# TestBench_rev3_6.net
KiCad netlist of a schematic drawn in EAGLE
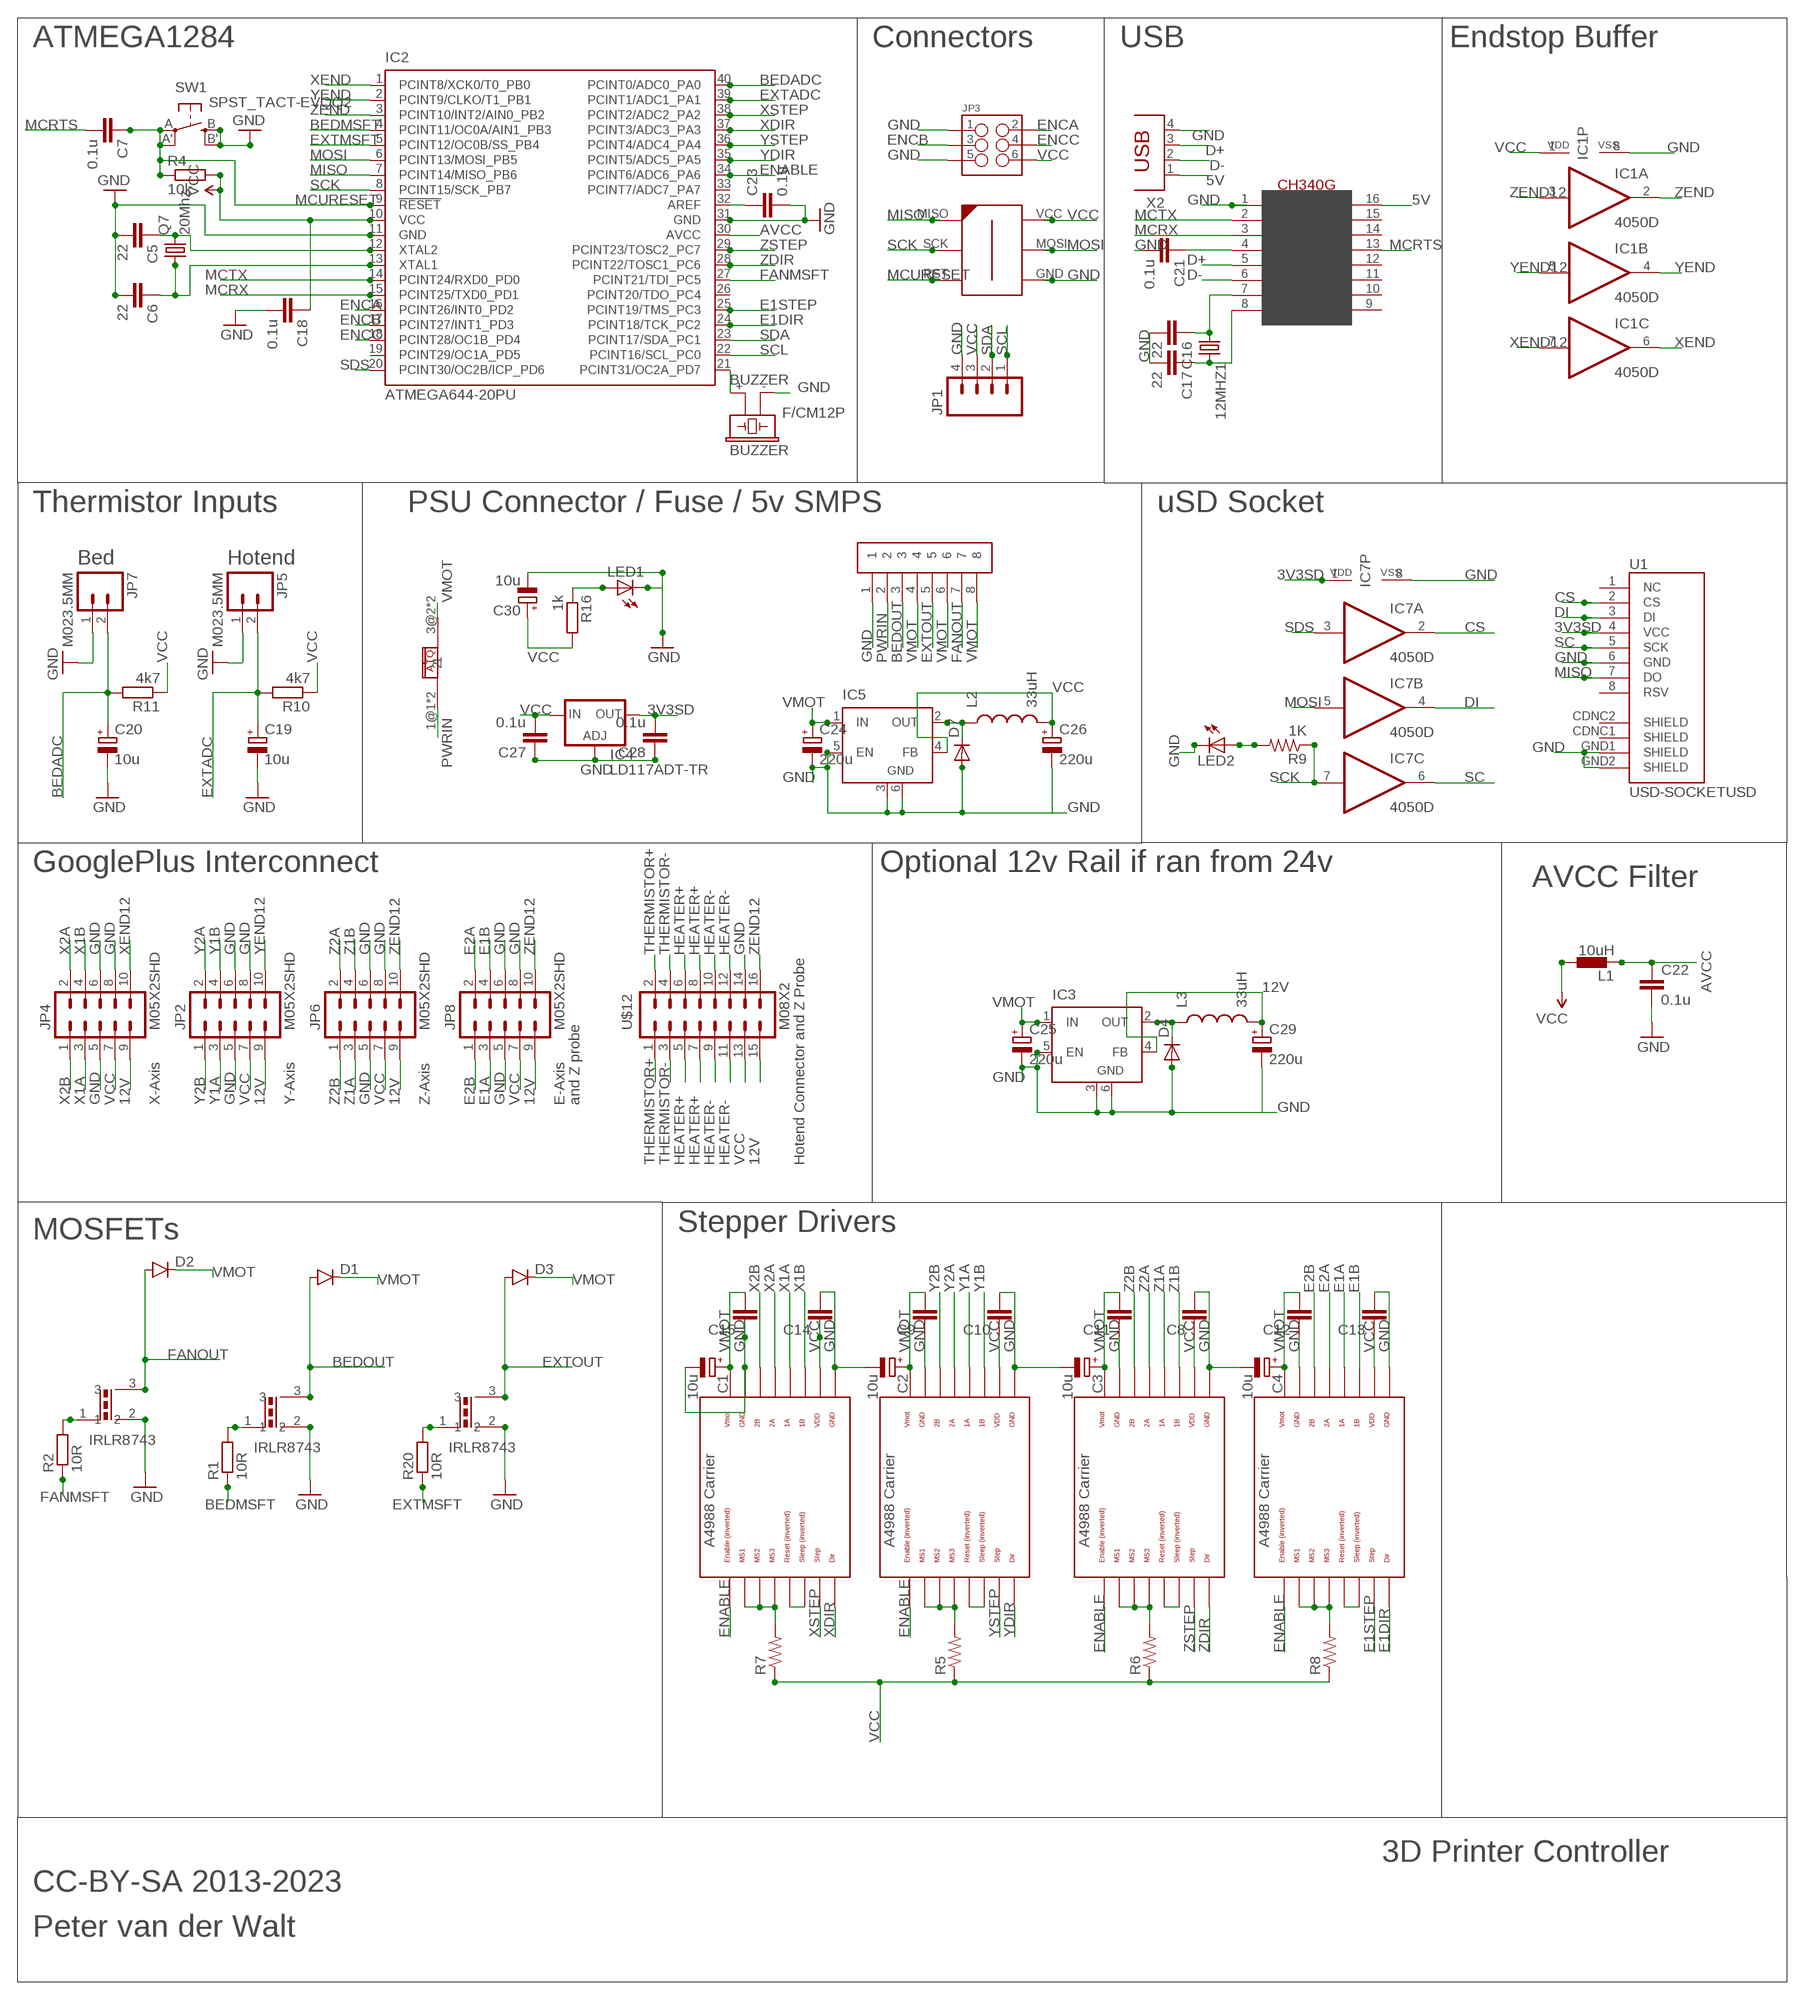
[diagram p0: schematic, sheet 1]

(export (version "E")
  (design (tool "Eeschema 10.0.6"))
  (components
    (comp (ref "12MHZ1")
      (value "CRYSTALHC49UP")
      (footprint "eagle-import:HC49UP")
      (libsource (lib "eagle-import") (part "crystal_CRYSTALHC49UP"))
    )
    (comp (ref "BUZZER")
      (value "F/CM12P")
      (footprint "eagle-import:F_CM12P")
      (libsource (lib "eagle-import") (part "F/CM12P"))
    )
    (comp (ref "C1")
      (value "10u")
      (footprint "eagle-import:SANYO-OSCON_SMD_B6")
      (libsource (lib "eagle-import") (part "CPOL-EUSANYO_SMD_B6"))
    )
    (comp (ref "C2")
      (value "10u")
      (footprint "eagle-import:SANYO-OSCON_SMD_B6")
      (libsource (lib "eagle-import") (part "CPOL-EUSANYO_SMD_B6"))
    )
    (comp (ref "C3")
      (value "10u")
      (footprint "eagle-import:SANYO-OSCON_SMD_B6")
      (libsource (lib "eagle-import") (part "CPOL-EUSANYO_SMD_B6"))
    )
    (comp (ref "C4")
      (value "10u")
      (footprint "eagle-import:SANYO-OSCON_SMD_B6")
      (libsource (lib "eagle-import") (part "CPOL-EUSANYO_SMD_B6"))
    )
    (comp (ref "C5")
      (value "22")
      (footprint "eagle-import:1206")
      (libsource (lib "eagle-import") (part "CAP1206"))
    )
    (comp (ref "C6")
      (value "22")
      (footprint "eagle-import:1206")
      (libsource (lib "eagle-import") (part "CAP1206"))
    )
    (comp (ref "C7")
      (value "0.1u")
      (footprint "eagle-import:1206")
      (libsource (lib "eagle-import") (part "CAP1206"))
    )
    (comp (ref "C8")
      (value "CAP1206")
      (footprint "eagle-import:1206")
      (libsource (lib "eagle-import") (part "CAP1206"))
    )
    (comp (ref "C9")
      (value "CAP1206")
      (footprint "eagle-import:1206")
      (libsource (lib "eagle-import") (part "CAP1206"))
    )
    (comp (ref "C10")
      (value "CAP1206")
      (footprint "eagle-import:1206")
      (libsource (lib "eagle-import") (part "CAP1206"))
    )
    (comp (ref "C11")
      (value "CAP1206")
      (footprint "eagle-import:1206")
      (libsource (lib "eagle-import") (part "CAP1206"))
    )
    (comp (ref "C12")
      (value "CAP1206")
      (footprint "eagle-import:1206")
      (libsource (lib "eagle-import") (part "CAP1206"))
    )
    (comp (ref "C13")
      (value "CAP1206")
      (footprint "eagle-import:1206")
      (libsource (lib "eagle-import") (part "CAP1206"))
    )
    (comp (ref "C14")
      (value "CAP1206")
      (footprint "eagle-import:1206")
      (libsource (lib "eagle-import") (part "CAP1206"))
    )
    (comp (ref "C15")
      (value "CAP1206")
      (footprint "eagle-import:1206")
      (libsource (lib "eagle-import") (part "CAP1206"))
    )
    (comp (ref "C16")
      (value "22")
      (footprint "eagle-import:1206")
      (libsource (lib "eagle-import") (part "CAP1206"))
    )
    (comp (ref "C17")
      (value "22")
      (footprint "eagle-import:1206")
      (libsource (lib "eagle-import") (part "CAP1206"))
    )
    (comp (ref "C18")
      (value "0.1u")
      (footprint "eagle-import:1206")
      (libsource (lib "eagle-import") (part "CAP1206"))
    )
    (comp (ref "C19")
      (value "10u")
      (footprint "eagle-import:SANYO-OSCON_SMD_B6")
      (libsource (lib "eagle-import") (part "CPOL-EUSANYO_SMD_B6"))
    )
    (comp (ref "C20")
      (value "10u")
      (footprint "eagle-import:SANYO-OSCON_SMD_B6")
      (libsource (lib "eagle-import") (part "CPOL-EUSANYO_SMD_B6"))
    )
    (comp (ref "C21")
      (value "0.1u")
      (footprint "eagle-import:1206")
      (libsource (lib "eagle-import") (part "CAP1206"))
    )
    (comp (ref "C22")
      (value "0.1u")
      (footprint "eagle-import:1206")
      (libsource (lib "eagle-import") (part "CAP1206"))
    )
    (comp (ref "C23")
      (value "0.1u")
      (footprint "eagle-import:1206")
      (libsource (lib "eagle-import") (part "CAP1206"))
    )
    (comp (ref "C24")
      (value "220u")
      (footprint "eagle-import:153CLV-0605")
      (libsource (lib "eagle-import") (part "CPOL-EU153CLV-0605"))
    )
    (comp (ref "C25")
      (value "220u")
      (footprint "eagle-import:153CLV-0605")
      (libsource (lib "eagle-import") (part "CPOL-EU153CLV-0605"))
    )
    (comp (ref "C26")
      (value "220u")
      (footprint "eagle-import:153CLV-0605")
      (libsource (lib "eagle-import") (part "CPOL-EU153CLV-0605"))
    )
    (comp (ref "C27")
      (value "0.1u")
      (footprint "eagle-import:1206")
      (libsource (lib "eagle-import") (part "CAP1206"))
    )
    (comp (ref "C28")
      (value "0.1u")
      (footprint "eagle-import:1206")
      (libsource (lib "eagle-import") (part "CAP1206"))
    )
    (comp (ref "C29")
      (value "220u")
      (footprint "eagle-import:153CLV-0605")
      (libsource (lib "eagle-import") (part "CPOL-EU153CLV-0605"))
    )
    (comp (ref "C30")
      (value "10u")
      (footprint "eagle-import:SANYO-OSCON_SMD_B6")
      (libsource (lib "eagle-import") (part "CPOL-EUSANYO_SMD_B6"))
    )
    (comp (ref "D1")
      (value "DIODESMA-ALT")
      (footprint "eagle-import:SMA-DIODE_ALT")
      (libsource (lib "eagle-import") (part "DIODESMA-ALT"))
    )
    (comp (ref "D2")
      (value "DIODESMA-ALT")
      (footprint "eagle-import:SMA-DIODE_ALT")
      (libsource (lib "eagle-import") (part "DIODESMA-ALT"))
    )
    (comp (ref "D3")
      (value "DIODESMA-ALT")
      (footprint "eagle-import:SMA-DIODE_ALT")
      (libsource (lib "eagle-import") (part "DIODESMA-ALT"))
    )
    (comp (ref "D4")
      (value "DIODE-DO-214AC")
      (footprint "eagle-import:DO-214AC")
      (libsource (lib "eagle-import") (part "DIODE-DO-214AC"))
    )
    (comp (ref "D7")
      (value "DIODE-DO-214AC")
      (footprint "eagle-import:DO-214AC")
      (libsource (lib "eagle-import") (part "DIODE-DO-214AC"))
    )
    (comp (ref "E1POL")
      (value "POLOLU_A4983CARRIER")
      (footprint "eagle-import:A4988BREAKOUT")
      (libsource (lib "eagle-import") (part "POLOLU_A4983CARRIER"))
    )
    (comp (ref "IC1")
      (value "4050D")
      (footprint "eagle-import:SO16")
      (libsource (lib "eagle-import") (part "4050D"))
    )
    (comp (ref "IC2")
      (value "ATMEGA644-20PU")
      (footprint "eagle-import:DIL40")
      (libsource (lib "eagle-import") (part "ATMEGA644-PU20"))
    )
    (comp (ref "IC3")
      (value "LM2596S")
      (footprint "eagle-import:TO263-5")
      (libsource (lib "eagle-import") (part "LM2596S"))
    )
    (comp (ref "IC4")
      (value "LD117ADT-TR")
      (footprint "eagle-import:DPACK")
      (libsource (lib "eagle-import") (part "LD117A?DT-TR"))
    )
    (comp (ref "IC5")
      (value "LM2596S")
      (footprint "eagle-import:TO263-5")
      (libsource (lib "eagle-import") (part "LM2596S"))
    )
    (comp (ref "IC7")
      (value "4050D")
      (footprint "eagle-import:SO16")
      (libsource (lib "eagle-import") (part "4050D"))
    )
    (comp (ref "JP1")
      (value "M04LOCK")
      (footprint "eagle-import:1X04_LOCK")
      (libsource (lib "eagle-import") (part "M04LOCK"))
    )
    (comp (ref "JP2")
      (value "M05X2SHD")
      (footprint "eagle-import:2X5-SHROUDED")
      (libsource (lib "eagle-import") (part "M05X2SHD"))
    )
    (comp (ref "JP3")
      (value "M03X2SHROUD")
      (footprint "eagle-import:2X3-SHROUDED")
      (libsource (lib "eagle-import") (part "M03X2SHROUD"))
    )
    (comp (ref "JP4")
      (value "M05X2SHD")
      (footprint "eagle-import:2X5-SHROUDED")
      (libsource (lib "eagle-import") (part "M05X2SHD"))
    )
    (comp (ref "JP5")
      (value "M023.5MM")
      (footprint "eagle-import:SCREWTERMINAL-3.5MM-2")
      (libsource (lib "eagle-import") (part "M023.5MM"))
    )
    (comp (ref "JP6")
      (value "M05X2SHD")
      (footprint "eagle-import:2X5-SHROUDED")
      (libsource (lib "eagle-import") (part "M05X2SHD"))
    )
    (comp (ref "JP7")
      (value "M023.5MM")
      (footprint "eagle-import:SCREWTERMINAL-3.5MM-2")
      (libsource (lib "eagle-import") (part "M023.5MM"))
    )
    (comp (ref "JP8")
      (value "M05X2SHD")
      (footprint "eagle-import:2X5-SHROUDED")
      (libsource (lib "eagle-import") (part "M05X2SHD"))
    )
    (comp (ref "L1")
      (value "10uH")
      (footprint "eagle-import:BL01RN1A")
      (libsource (lib "eagle-import") (part "BL01RN1A"))
    )
    (comp (ref "L2")
      (value "33uH")
      (footprint "eagle-import:CDRH125")
      (libsource (lib "eagle-import") (part "INDUCTORPWR"))
    )
    (comp (ref "L3")
      (value "33uH")
      (footprint "eagle-import:CDRH125")
      (libsource (lib "eagle-import") (part "INDUCTORPWR"))
    )
    (comp (ref "LED1")
      (value "LEDSMT1206")
      (footprint "eagle-import:1206")
      (libsource (lib "eagle-import") (part "LEDSMT1206"))
    )
    (comp (ref "LED2")
      (value "LEDSMT1206")
      (footprint "eagle-import:1206")
      (libsource (lib "eagle-import") (part "LEDSMT1206"))
    )
    (comp (ref "Q7")
      (value "20Mhz")
      (footprint "eagle-import:HC49UP")
      (fields (field (name "OC_FARNELL") "unknown") (field (name "OC_NEWARK") "unknown"))
      (libsource (lib "eagle-import") (part "CRYSTALHC49UP"))
    )
    (comp (ref "R1")
      (value "10R")
      (footprint "eagle-import:M1206")
      (libsource (lib "eagle-import") (part "R-EU_M1206"))
    )
    (comp (ref "R2")
      (value "10R")
      (footprint "eagle-import:M1206")
      (libsource (lib "eagle-import") (part "R-EU_M1206"))
    )
    (comp (ref "R4")
      (value "10k")
      (footprint "eagle-import:M1206")
      (libsource (lib "eagle-import") (part "R-EU_M1206"))
    )
    (comp (ref "R5")
      (value "RESISTOR1206")
      (footprint "eagle-import:1206")
      (libsource (lib "eagle-import") (part "RESISTOR1206"))
    )
    (comp (ref "R6")
      (value "RESISTOR1206")
      (footprint "eagle-import:1206")
      (libsource (lib "eagle-import") (part "RESISTOR1206"))
    )
    (comp (ref "R7")
      (value "RESISTOR1206")
      (footprint "eagle-import:1206")
      (libsource (lib "eagle-import") (part "RESISTOR1206"))
    )
    (comp (ref "R8")
      (value "RESISTOR1206")
      (footprint "eagle-import:1206")
      (libsource (lib "eagle-import") (part "RESISTOR1206"))
    )
    (comp (ref "R9")
      (value "1K")
      (footprint "eagle-import:M1206")
      (libsource (lib "eagle-import") (part "R-US_M1206"))
    )
    (comp (ref "R10")
      (value "4k7")
      (footprint "eagle-import:M1206")
      (libsource (lib "eagle-import") (part "R-EU_M1206"))
    )
    (comp (ref "R11")
      (value "4k7")
      (footprint "eagle-import:M1206")
      (libsource (lib "eagle-import") (part "R-EU_M1206"))
    )
    (comp (ref "R16")
      (value "1k")
      (footprint "eagle-import:M1206")
      (libsource (lib "eagle-import") (part "R-EU_M1206"))
    )
    (comp (ref "R20")
      (value "10R")
      (footprint "eagle-import:M1206")
      (libsource (lib "eagle-import") (part "R-EU_M1206"))
    )
    (comp (ref "SW1")
      (value "SPST_TACT-EVQQ2")
      (footprint "eagle-import:EVQ-Q2")
      (libsource (lib "eagle-import") (part "SPST_TACT-EVQQ2"))
    )
    (comp (ref "U$1")
      (value "IRLR8743")
      (footprint "eagle-import:TO263")
      (libsource (lib "eagle-import") (part "IRLR8743"))
    )
    (comp (ref "U$2")
      (value "CH340G")
      (footprint "eagle-import:SOIC16")
      (libsource (lib "eagle-import") (part "CH340G"))
    )
    (comp (ref "U$3")
      (value "IRLR8743")
      (footprint "eagle-import:TO263")
      (libsource (lib "eagle-import") (part "IRLR8743"))
    )
    (comp (ref "U$4")
      (value "IRLR8743")
      (footprint "eagle-import:TO263")
      (libsource (lib "eagle-import") (part "IRLR8743"))
    )
    (comp (ref "U$5")
      (value "XY825A-8P")
      (footprint "eagle-import:XY825A-8P")
      (libsource (lib "eagle-import") (part "XY825A-8P"))
    )
    (comp (ref "U$6")
      (value "CQ-121")
      (footprint "eagle-import:CQ121")
      (libsource (lib "eagle-import") (part "CQ-121"))
    )
    (comp (ref "U$7")
      (value "AVR-ISP-6-EDGE")
      (footprint "eagle-import:6PAD_ISP")
      (libsource (lib "eagle-import") (part "AVR-ISP-6-EDGE"))
    )
    (comp (ref "U$12")
      (value "M08X2")
      (footprint "eagle-import:2X8")
      (libsource (lib "eagle-import") (part "M08X2"))
    )
    (comp (ref "U1")
      (value "USD-SOCKETUSD")
      (footprint "eagle-import:USD-SOCKET-PP")
      (libsource (lib "eagle-import") (part "USD-SOCKETUSD"))
    )
    (comp (ref "X2")
      (value "PN61729")
      (footprint "eagle-import:PN61729")
      (libsource (lib "eagle-import") (part "PN61729"))
    )
    (comp (ref "XPOL")
      (value "POLOLU_A4983CARRIER")
      (footprint "eagle-import:A4988BREAKOUT")
      (libsource (lib "eagle-import") (part "POLOLU_A4983CARRIER"))
    )
    (comp (ref "YPOL")
      (value "POLOLU_A4983CARRIER")
      (footprint "eagle-import:A4988BREAKOUT")
      (libsource (lib "eagle-import") (part "POLOLU_A4983CARRIER"))
    )
    (comp (ref "ZPOL")
      (value "POLOLU_A4983CARRIER")
      (footprint "eagle-import:A4988BREAKOUT")
      (libsource (lib "eagle-import") (part "POLOLU_A4983CARRIER"))
    )
  )
  (nets
    (net (code "1") (name "/3V3SD") (class "Default")
      (node (ref "C28") (pin "2") (pinfunction "2_2") (pintype "passive"))
      (node (ref "IC4") (pin "4") (pinfunction "OUT_4") (pintype "passive"))
      (node (ref "IC7") (pin "1") (pinfunction "VDD_1") (pintype "power_in"))
      (node (ref "U1") (pin "4") (pinfunction "VCC_4") (pintype "bidirectional"))
    )
    (net (code "2") (name "/5V") (class "Default")
      (node (ref "U$2") (pin "16") (pinfunction "VCC_16") (pintype "bidirectional"))
      (node (ref "X2") (pin "1") (pinfunction "1_1") (pintype "passive"))
    )
    (net (code "3") (name "/12V") (class "Default")
      (node (ref "C29") (pin "+") (pinfunction "+_+") (pintype "passive"))
      (node (ref "IC3") (pin "4") (pinfunction "FB_4") (pintype "input"))
      (node (ref "JP2") (pin "9") (pinfunction "9_9") (pintype "passive"))
      (node (ref "JP4") (pin "9") (pinfunction "9_9") (pintype "passive"))
      (node (ref "JP6") (pin "9") (pinfunction "9_9") (pintype "passive"))
      (node (ref "JP8") (pin "9") (pinfunction "9_9") (pintype "passive"))
      (node (ref "L3") (pin "2") (pinfunction "2_2") (pintype "passive"))
      (node (ref "U$12") (pin "15") (pinfunction "15_15") (pintype "passive"))
    )
    (net (code "4") (name "/AVCC") (class "Default")
      (node (ref "C22") (pin "1") (pinfunction "1_1") (pintype "passive"))
      (node (ref "IC2") (pin "30") (pinfunction "AVCC_30") (pintype "power_in"))
      (node (ref "L1") (pin "1") (pinfunction "1_1") (pintype "passive"))
    )
    (net (code "5") (name "/BEDADC") (class "Default")
      (node (ref "C20") (pin "+") (pinfunction "+_+") (pintype "passive"))
      (node (ref "IC2") (pin "40") (pinfunction "PCINT0/ADC0_PA0_40") (pintype "bidirectional"))
      (node (ref "JP7") (pin "2") (pinfunction "2_2") (pintype "passive"))
      (node (ref "R11") (pin "2") (pinfunction "2_2") (pintype "passive"))
    )
    (net (code "6") (name "/BEDMSFT") (class "Default")
      (node (ref "IC2") (pin "4") (pinfunction "PCINT11/OC0A/AIN1_PB3_4") (pintype "bidirectional"))
      (node (ref "R1") (pin "1") (pinfunction "1_1") (pintype "passive"))
    )
    (net (code "7") (name "/BEDOUT") (class "Default")
      (node (ref "D1") (pin "A") (pinfunction "A_A") (pintype "passive"))
      (node (ref "U$3") (pin "3") (pinfunction "3_3") (pintype "bidirectional"))
      (node (ref "U$5") (pin "3") (pinfunction "3_3") (pintype "bidirectional"))
    )
    (net (code "8") (name "/BUZZER") (class "Default")
      (node (ref "BUZZER") (pin "+") (pinfunction "1_+") (pintype "passive"))
      (node (ref "IC2") (pin "21") (pinfunction "PCINT31/OC2A_PD7_21") (pintype "bidirectional"))
    )
    (net (code "9") (name "/CS") (class "Default")
      (node (ref "IC7") (pin "2") (pinfunction "O_2") (pintype "output"))
      (node (ref "U1") (pin "2") (pinfunction "CS_2") (pintype "bidirectional"))
    )
    (net (code "10") (name "/D+") (class "Default")
      (node (ref "U$2") (pin "5") (pinfunction "D+_5") (pintype "bidirectional"))
      (node (ref "X2") (pin "3") (pinfunction "3_3") (pintype "passive"))
    )
    (net (code "11") (name "/D-") (class "Default")
      (node (ref "U$2") (pin "6") (pinfunction "D-_6") (pintype "bidirectional"))
      (node (ref "X2") (pin "2") (pinfunction "2_2") (pintype "passive"))
    )
    (net (code "12") (name "/DI") (class "Default")
      (node (ref "IC7") (pin "4") (pinfunction "O_4") (pintype "output"))
      (node (ref "U1") (pin "3") (pinfunction "DI_3") (pintype "bidirectional"))
    )
    (net (code "13") (name "/E1A") (class "Default")
      (node (ref "E1POL") (pin "1A") (pinfunction "1A_1A") (pintype "output"))
      (node (ref "JP8") (pin "3") (pinfunction "3_3") (pintype "passive"))
    )
    (net (code "14") (name "/E1B") (class "Default")
      (node (ref "E1POL") (pin "1B") (pinfunction "1B_1B") (pintype "output"))
      (node (ref "JP8") (pin "4") (pinfunction "4_4") (pintype "passive"))
    )
    (net (code "15") (name "/E1DIR") (class "Default")
      (node (ref "E1POL") (pin "DIR") (pinfunction "DIR_DIR") (pintype "input"))
      (node (ref "IC2") (pin "24") (pinfunction "PCINT18/TCK_PC2_24") (pintype "bidirectional"))
    )
    (net (code "16") (name "/E1STEP") (class "Default")
      (node (ref "E1POL") (pin "STEP") (pinfunction "STEP_STEP") (pintype "input"))
      (node (ref "IC2") (pin "25") (pinfunction "PCINT19/TMS_PC3_25") (pintype "bidirectional"))
    )
    (net (code "17") (name "/E2A") (class "Default")
      (node (ref "E1POL") (pin "2A") (pinfunction "2A_2A") (pintype "output"))
      (node (ref "JP8") (pin "2") (pinfunction "2_2") (pintype "passive"))
    )
    (net (code "18") (name "/E2B") (class "Default")
      (node (ref "E1POL") (pin "2B") (pinfunction "2B_2B") (pintype "output"))
      (node (ref "JP8") (pin "1") (pinfunction "1_1") (pintype "passive"))
    )
    (net (code "19") (name "/ENABLE") (class "Default")
      (node (ref "E1POL") (pin "EN") (pinfunction "EN_EN") (pintype "input"))
      (node (ref "IC2") (pin "34") (pinfunction "PCINT6/ADC6_PA6_34") (pintype "bidirectional"))
      (node (ref "XPOL") (pin "EN") (pinfunction "EN_EN") (pintype "input"))
      (node (ref "YPOL") (pin "EN") (pinfunction "EN_EN") (pintype "input"))
      (node (ref "ZPOL") (pin "EN") (pinfunction "EN_EN") (pintype "input"))
    )
    (net (code "20") (name "/ENCA") (class "Default")
      (node (ref "IC2") (pin "16") (pinfunction "PCINT26/INT0_PD2_16") (pintype "bidirectional"))
      (node (ref "JP3") (pin "2") (pinfunction "2_2") (pintype "bidirectional"))
    )
    (net (code "21") (name "/ENCB") (class "Default")
      (node (ref "IC2") (pin "17") (pinfunction "PCINT27/INT1_PD3_17") (pintype "bidirectional"))
      (node (ref "JP3") (pin "3") (pinfunction "3_3") (pintype "bidirectional"))
    )
    (net (code "22") (name "/ENCC") (class "Default")
      (node (ref "IC2") (pin "18") (pinfunction "PCINT28/OC1B_PD4_18") (pintype "bidirectional"))
      (node (ref "JP3") (pin "4") (pinfunction "4_4") (pintype "bidirectional"))
    )
    (net (code "23") (name "/EXTADC") (class "Default")
      (node (ref "C19") (pin "+") (pinfunction "+_+") (pintype "passive"))
      (node (ref "IC2") (pin "39") (pinfunction "PCINT1/ADC1_PA1_39") (pintype "bidirectional"))
      (node (ref "JP5") (pin "2") (pinfunction "2_2") (pintype "passive"))
      (node (ref "R10") (pin "2") (pinfunction "2_2") (pintype "passive"))
    )
    (net (code "24") (name "/EXTMSFT") (class "Default")
      (node (ref "IC2") (pin "5") (pinfunction "PCINT12/OC0B/SS_PB4_5") (pintype "bidirectional"))
      (node (ref "R20") (pin "1") (pinfunction "1_1") (pintype "passive"))
    )
    (net (code "25") (name "/EXTOUT") (class "Default")
      (node (ref "D3") (pin "A") (pinfunction "A_A") (pintype "passive"))
      (node (ref "U$1") (pin "3") (pinfunction "3_3") (pintype "bidirectional"))
      (node (ref "U$5") (pin "5") (pinfunction "5_5") (pintype "bidirectional"))
    )
    (net (code "26") (name "/FANMSFT") (class "Default")
      (node (ref "IC2") (pin "27") (pinfunction "PCINT21/TDI_PC5_27") (pintype "bidirectional"))
      (node (ref "R2") (pin "1") (pinfunction "1_1") (pintype "passive"))
    )
    (net (code "27") (name "/FANOUT") (class "Default")
      (node (ref "D2") (pin "A") (pinfunction "A_A") (pintype "passive"))
      (node (ref "U$4") (pin "3") (pinfunction "3_3") (pintype "bidirectional"))
      (node (ref "U$5") (pin "7") (pinfunction "7_7") (pintype "bidirectional"))
    )
    (net (code "28") (name "/HEATER+") (class "Default")
      (node (ref "U$12") (pin "5") (pinfunction "5_5") (pintype "passive"))
      (node (ref "U$12") (pin "6") (pinfunction "6_6") (pintype "passive"))
      (node (ref "U$12") (pin "7") (pinfunction "7_7") (pintype "passive"))
      (node (ref "U$12") (pin "8") (pinfunction "8_8") (pintype "passive"))
    )
    (net (code "29") (name "/HEATER-") (class "Default")
      (node (ref "U$12") (pin "10") (pinfunction "10_10") (pintype "passive"))
      (node (ref "U$12") (pin "11") (pinfunction "11_11") (pintype "passive"))
      (node (ref "U$12") (pin "12") (pinfunction "12_12") (pintype "passive"))
      (node (ref "U$12") (pin "9") (pinfunction "9_9") (pintype "passive"))
    )
    (net (code "30") (name "/MCRTS") (class "Default")
      (node (ref "C7") (pin "2") (pinfunction "2_2") (pintype "passive"))
      (node (ref "U$2") (pin "13") (pinfunction "DTR_13") (pintype "bidirectional"))
    )
    (net (code "31") (name "/MCRX") (class "Default")
      (node (ref "IC2") (pin "15") (pinfunction "PCINT25/TXD0_PD1_15") (pintype "bidirectional"))
      (node (ref "U$2") (pin "3") (pinfunction "RX_3") (pintype "bidirectional"))
    )
    (net (code "32") (name "/MCTX") (class "Default")
      (node (ref "IC2") (pin "14") (pinfunction "PCINT24/RXD0_PD0_14") (pintype "bidirectional"))
      (node (ref "U$2") (pin "2") (pinfunction "TX_2") (pintype "bidirectional"))
    )
    (net (code "33") (name "/MCURESET") (class "Default")
      (node (ref "C7") (pin "1") (pinfunction "1_1") (pintype "passive"))
      (node (ref "IC2") (pin "9") (pinfunction "~{RESET}_9") (pintype "input"))
      (node (ref "R4") (pin "1") (pinfunction "1_1") (pintype "passive"))
      (node (ref "SW1") (pin "A") (pinfunction "P_A") (pintype "passive"))
      (node (ref "SW1") (pin "A'") (pinfunction "P1_A'") (pintype "passive"))
      (node (ref "U$7") (pin "RST") (pinfunction "P$3_RST") (pintype "bidirectional"))
    )
    (net (code "34") (name "/MISO") (class "Default")
      (node (ref "IC2") (pin "7") (pinfunction "PCINT14/MISO_PB6_7") (pintype "bidirectional"))
      (node (ref "U$7") (pin "MISO") (pinfunction "P$1_MISO") (pintype "bidirectional"))
      (node (ref "U1") (pin "7") (pinfunction "DO_7") (pintype "bidirectional"))
    )
    (net (code "35") (name "/MOSI") (class "Default")
      (node (ref "IC2") (pin "6") (pinfunction "PCINT13/MOSI_PB5_6") (pintype "bidirectional"))
      (node (ref "IC7") (pin "5") (pinfunction "I_5") (pintype "input"))
      (node (ref "U$7") (pin "MOSI") (pinfunction "P$5_MOSI") (pintype "bidirectional"))
    )
    (net (code "36") (name "/PWRIN") (class "Default")
      (node (ref "U$5") (pin "2") (pinfunction "2_2") (pintype "bidirectional"))
      (node (ref "U$6") (pin "1@1") (pinfunction "1_1@1") (pintype "bidirectional"))
      (node (ref "U$6") (pin "2@1") (pinfunction "1_2@1") (pintype "bidirectional"))
    )
    (net (code "37") (name "/SC") (class "Default")
      (node (ref "IC7") (pin "6") (pinfunction "O_6") (pintype "output"))
      (node (ref "U1") (pin "5") (pinfunction "SCK_5") (pintype "bidirectional"))
    )
    (net (code "38") (name "/SCK") (class "Default")
      (node (ref "IC2") (pin "8") (pinfunction "PCINT15/SCK_PB7_8") (pintype "bidirectional"))
      (node (ref "IC7") (pin "7") (pinfunction "I_7") (pintype "input"))
      (node (ref "R9") (pin "1") (pinfunction "1_1") (pintype "passive"))
      (node (ref "U$7") (pin "SCK") (pinfunction "P$2_SCK") (pintype "bidirectional"))
    )
    (net (code "39") (name "/SCL") (class "Default")
      (node (ref "IC2") (pin "22") (pinfunction "PCINT16/SCL_PC0_22") (pintype "bidirectional"))
      (node (ref "JP1") (pin "1") (pinfunction "1_1") (pintype "passive"))
    )
    (net (code "40") (name "/SDA") (class "Default")
      (node (ref "IC2") (pin "23") (pinfunction "PCINT17/SDA_PC1_23") (pintype "bidirectional"))
      (node (ref "JP1") (pin "2") (pinfunction "2_2") (pintype "passive"))
    )
    (net (code "41") (name "/SDS") (class "Default")
      (node (ref "IC2") (pin "20") (pinfunction "PCINT30/OC2B/ICP_PD6_20") (pintype "bidirectional"))
      (node (ref "IC7") (pin "3") (pinfunction "I_3") (pintype "input"))
    )
    (net (code "42") (name "/THERMISTOR+") (class "Default")
      (node (ref "U$12") (pin "1") (pinfunction "1_1") (pintype "passive"))
      (node (ref "U$12") (pin "2") (pinfunction "2_2") (pintype "passive"))
    )
    (net (code "43") (name "/THERMISTOR-") (class "Default")
      (node (ref "U$12") (pin "3") (pinfunction "3_3") (pintype "passive"))
      (node (ref "U$12") (pin "4") (pinfunction "4_4") (pintype "passive"))
    )
    (net (code "44") (name "/VMOT") (class "Default")
      (node (ref "C1") (pin "+") (pinfunction "+_+") (pintype "passive"))
      (node (ref "C11") (pin "2") (pinfunction "2_2") (pintype "passive"))
      (node (ref "C12") (pin "2") (pinfunction "2_2") (pintype "passive"))
      (node (ref "C15") (pin "2") (pinfunction "2_2") (pintype "passive"))
      (node (ref "C2") (pin "+") (pinfunction "+_+") (pintype "passive"))
      (node (ref "C24") (pin "+") (pinfunction "+_+") (pintype "passive"))
      (node (ref "C25") (pin "+") (pinfunction "+_+") (pintype "passive"))
      (node (ref "C3") (pin "+") (pinfunction "+_+") (pintype "passive"))
      (node (ref "C4") (pin "+") (pinfunction "+_+") (pintype "passive"))
      (node (ref "C9") (pin "2") (pinfunction "2_2") (pintype "passive"))
      (node (ref "D1") (pin "C") (pinfunction "C_C") (pintype "passive"))
      (node (ref "D2") (pin "C") (pinfunction "C_C") (pintype "passive"))
      (node (ref "D3") (pin "C") (pinfunction "C_C") (pintype "passive"))
      (node (ref "E1POL") (pin "VMOT") (pinfunction "VMOT_VMOT") (pintype "power_in"))
      (node (ref "IC3") (pin "1") (pinfunction "IN_1") (pintype "input"))
      (node (ref "IC5") (pin "1") (pinfunction "IN_1") (pintype "input"))
      (node (ref "U$5") (pin "4") (pinfunction "4_4") (pintype "bidirectional"))
      (node (ref "U$5") (pin "6") (pinfunction "6_6") (pintype "bidirectional"))
      (node (ref "U$5") (pin "8") (pinfunction "8_8") (pintype "bidirectional"))
      (node (ref "U$6") (pin "3@2") (pinfunction "2_3@2") (pintype "bidirectional"))
      (node (ref "U$6") (pin "4@2") (pinfunction "2_4@2") (pintype "bidirectional"))
      (node (ref "XPOL") (pin "VMOT") (pinfunction "VMOT_VMOT") (pintype "power_in"))
      (node (ref "YPOL") (pin "VMOT") (pinfunction "VMOT_VMOT") (pintype "power_in"))
      (node (ref "ZPOL") (pin "VMOT") (pinfunction "VMOT_VMOT") (pintype "power_in"))
    )
    (net (code "45") (name "/X1A") (class "Default")
      (node (ref "JP4") (pin "3") (pinfunction "3_3") (pintype "passive"))
      (node (ref "XPOL") (pin "1A") (pinfunction "1A_1A") (pintype "output"))
    )
    (net (code "46") (name "/X1B") (class "Default")
      (node (ref "JP4") (pin "4") (pinfunction "4_4") (pintype "passive"))
      (node (ref "XPOL") (pin "1B") (pinfunction "1B_1B") (pintype "output"))
    )
    (net (code "47") (name "/X2A") (class "Default")
      (node (ref "JP4") (pin "2") (pinfunction "2_2") (pintype "passive"))
      (node (ref "XPOL") (pin "2A") (pinfunction "2A_2A") (pintype "output"))
    )
    (net (code "48") (name "/X2B") (class "Default")
      (node (ref "JP4") (pin "1") (pinfunction "1_1") (pintype "passive"))
      (node (ref "XPOL") (pin "2B") (pinfunction "2B_2B") (pintype "output"))
    )
    (net (code "49") (name "/XDIR") (class "Default")
      (node (ref "IC2") (pin "37") (pinfunction "PCINT3/ADC3_PA3_37") (pintype "bidirectional"))
      (node (ref "XPOL") (pin "DIR") (pinfunction "DIR_DIR") (pintype "input"))
    )
    (net (code "50") (name "/XEND") (class "Default")
      (node (ref "IC1") (pin "6") (pinfunction "O_6") (pintype "output"))
      (node (ref "IC2") (pin "1") (pinfunction "PCINT8/XCK0/T0_PB0_1") (pintype "bidirectional"))
    )
    (net (code "51") (name "/XEND12") (class "Default")
      (node (ref "IC1") (pin "7") (pinfunction "I_7") (pintype "input"))
      (node (ref "JP4") (pin "10") (pinfunction "10_10") (pintype "passive"))
    )
    (net (code "52") (name "/XSTEP") (class "Default")
      (node (ref "IC2") (pin "38") (pinfunction "PCINT2/ADC2_PA2_38") (pintype "bidirectional"))
      (node (ref "XPOL") (pin "STEP") (pinfunction "STEP_STEP") (pintype "input"))
    )
    (net (code "53") (name "/Y1A") (class "Default")
      (node (ref "JP2") (pin "3") (pinfunction "3_3") (pintype "passive"))
      (node (ref "YPOL") (pin "1A") (pinfunction "1A_1A") (pintype "output"))
    )
    (net (code "54") (name "/Y1B") (class "Default")
      (node (ref "JP2") (pin "4") (pinfunction "4_4") (pintype "passive"))
      (node (ref "YPOL") (pin "1B") (pinfunction "1B_1B") (pintype "output"))
    )
    (net (code "55") (name "/Y2A") (class "Default")
      (node (ref "JP2") (pin "2") (pinfunction "2_2") (pintype "passive"))
      (node (ref "YPOL") (pin "2A") (pinfunction "2A_2A") (pintype "output"))
    )
    (net (code "56") (name "/Y2B") (class "Default")
      (node (ref "JP2") (pin "1") (pinfunction "1_1") (pintype "passive"))
      (node (ref "YPOL") (pin "2B") (pinfunction "2B_2B") (pintype "output"))
    )
    (net (code "57") (name "/YDIR") (class "Default")
      (node (ref "IC2") (pin "35") (pinfunction "PCINT5/ADC5_PA5_35") (pintype "bidirectional"))
      (node (ref "YPOL") (pin "DIR") (pinfunction "DIR_DIR") (pintype "input"))
    )
    (net (code "58") (name "/YEND") (class "Default")
      (node (ref "IC1") (pin "4") (pinfunction "O_4") (pintype "output"))
      (node (ref "IC2") (pin "2") (pinfunction "PCINT9/CLKO/T1_PB1_2") (pintype "bidirectional"))
    )
    (net (code "59") (name "/YEND12") (class "Default")
      (node (ref "IC1") (pin "5") (pinfunction "I_5") (pintype "input"))
      (node (ref "JP2") (pin "10") (pinfunction "10_10") (pintype "passive"))
    )
    (net (code "60") (name "/YSTEP") (class "Default")
      (node (ref "IC2") (pin "36") (pinfunction "PCINT4/ADC4_PA4_36") (pintype "bidirectional"))
      (node (ref "YPOL") (pin "STEP") (pinfunction "STEP_STEP") (pintype "input"))
    )
    (net (code "61") (name "/Z1A") (class "Default")
      (node (ref "JP6") (pin "3") (pinfunction "3_3") (pintype "passive"))
      (node (ref "ZPOL") (pin "1A") (pinfunction "1A_1A") (pintype "output"))
    )
    (net (code "62") (name "/Z1B") (class "Default")
      (node (ref "JP6") (pin "4") (pinfunction "4_4") (pintype "passive"))
      (node (ref "ZPOL") (pin "1B") (pinfunction "1B_1B") (pintype "output"))
    )
    (net (code "63") (name "/Z2A") (class "Default")
      (node (ref "JP6") (pin "2") (pinfunction "2_2") (pintype "passive"))
      (node (ref "ZPOL") (pin "2A") (pinfunction "2A_2A") (pintype "output"))
    )
    (net (code "64") (name "/Z2B") (class "Default")
      (node (ref "JP6") (pin "1") (pinfunction "1_1") (pintype "passive"))
      (node (ref "ZPOL") (pin "2B") (pinfunction "2B_2B") (pintype "output"))
    )
    (net (code "65") (name "/ZDIR") (class "Default")
      (node (ref "IC2") (pin "28") (pinfunction "PCINT22/TOSC1_PC6_28") (pintype "bidirectional"))
      (node (ref "ZPOL") (pin "DIR") (pinfunction "DIR_DIR") (pintype "input"))
    )
    (net (code "66") (name "/ZEND") (class "Default")
      (node (ref "IC1") (pin "2") (pinfunction "O_2") (pintype "output"))
      (node (ref "IC2") (pin "3") (pinfunction "PCINT10/INT2/AIN0_PB2_3") (pintype "bidirectional"))
    )
    (net (code "67") (name "/ZEND12") (class "Default")
      (node (ref "IC1") (pin "3") (pinfunction "I_3") (pintype "input"))
      (node (ref "JP6") (pin "10") (pinfunction "10_10") (pintype "passive"))
      (node (ref "JP8") (pin "10") (pinfunction "10_10") (pintype "passive"))
      (node (ref "U$12") (pin "16") (pinfunction "16_16") (pintype "passive"))
    )
    (net (code "68") (name "/ZSTEP") (class "Default")
      (node (ref "IC2") (pin "29") (pinfunction "PCINT23/TOSC2_PC7_29") (pintype "bidirectional"))
      (node (ref "ZPOL") (pin "STEP") (pinfunction "STEP_STEP") (pintype "input"))
    )
    (net (code "69") (name "GND") (class "Default")
      (node (ref "BUZZER") (pin "-") (pinfunction "2_-") (pintype "passive"))
      (node (ref "C1") (pin "-") (pinfunction "-_-") (pintype "passive"))
      (node (ref "C10") (pin "2") (pinfunction "2_2") (pintype "passive"))
      (node (ref "C11") (pin "1") (pinfunction "1_1") (pintype "passive"))
      (node (ref "C12") (pin "1") (pinfunction "1_1") (pintype "passive"))
      (node (ref "C13") (pin "2") (pinfunction "2_2") (pintype "passive"))
      (node (ref "C14") (pin "2") (pinfunction "2_2") (pintype "passive"))
      (node (ref "C15") (pin "1") (pinfunction "1_1") (pintype "passive"))
      (node (ref "C16") (pin "2") (pinfunction "2_2") (pintype "passive"))
      (node (ref "C17") (pin "2") (pinfunction "2_2") (pintype "passive"))
      (node (ref "C18") (pin "2") (pinfunction "2_2") (pintype "passive"))
      (node (ref "C19") (pin "-") (pinfunction "-_-") (pintype "passive"))
      (node (ref "C2") (pin "-") (pinfunction "-_-") (pintype "passive"))
      (node (ref "C20") (pin "-") (pinfunction "-_-") (pintype "passive"))
      (node (ref "C21") (pin "2") (pinfunction "2_2") (pintype "passive"))
      (node (ref "C22") (pin "2") (pinfunction "2_2") (pintype "passive"))
      (node (ref "C23") (pin "2") (pinfunction "2_2") (pintype "passive"))
      (node (ref "C24") (pin "-") (pinfunction "-_-") (pintype "passive"))
      (node (ref "C25") (pin "-") (pinfunction "-_-") (pintype "passive"))
      (node (ref "C26") (pin "-") (pinfunction "-_-") (pintype "passive"))
      (node (ref "C27") (pin "1") (pinfunction "1_1") (pintype "passive"))
      (node (ref "C28") (pin "1") (pinfunction "1_1") (pintype "passive"))
      (node (ref "C29") (pin "-") (pinfunction "-_-") (pintype "passive"))
      (node (ref "C3") (pin "-") (pinfunction "-_-") (pintype "passive"))
      (node (ref "C30") (pin "-") (pinfunction "-_-") (pintype "passive"))
      (node (ref "C4") (pin "-") (pinfunction "-_-") (pintype "passive"))
      (node (ref "C5") (pin "2") (pinfunction "2_2") (pintype "passive"))
      (node (ref "C6") (pin "2") (pinfunction "2_2") (pintype "passive"))
      (node (ref "C8") (pin "2") (pinfunction "2_2") (pintype "passive"))
      (node (ref "C9") (pin "1") (pinfunction "1_1") (pintype "passive"))
      (node (ref "D4") (pin "2") (pinfunction "A_2") (pintype "passive"))
      (node (ref "D7") (pin "2") (pinfunction "A_2") (pintype "passive"))
      (node (ref "E1POL") (pin "GND") (pinfunction "GND_GND") (pintype "power_in"))
      (node (ref "E1POL") (pin "GND@0") (pinfunction "GND_GND@0") (pintype "power_in"))
      (node (ref "IC1") (pin "8") (pinfunction "VSS_8") (pintype "power_in"))
      (node (ref "IC2") (pin "11") (pinfunction "GND_11") (pintype "power_in"))
      (node (ref "IC2") (pin "31") (pinfunction "GND_31") (pintype "power_in"))
      (node (ref "IC3") (pin "3") (pinfunction "GND_3") (pintype "power_in"))
      (node (ref "IC3") (pin "5") (pinfunction "EN_5") (pintype "input"))
      (node (ref "IC3") (pin "6") (pinfunction "GND_6") (pintype "power_in"))
      (node (ref "IC4") (pin "1") (pinfunction "ADJ_1") (pintype "input"))
      (node (ref "IC5") (pin "3") (pinfunction "GND_3") (pintype "power_in"))
      (node (ref "IC5") (pin "5") (pinfunction "EN_5") (pintype "input"))
      (node (ref "IC5") (pin "6") (pinfunction "GND_6") (pintype "power_in"))
      (node (ref "IC7") (pin "8") (pinfunction "VSS_8") (pintype "power_in"))
      (node (ref "JP1") (pin "4") (pinfunction "4_4") (pintype "passive"))
      (node (ref "JP2") (pin "5") (pinfunction "5_5") (pintype "passive"))
      (node (ref "JP2") (pin "6") (pinfunction "6_6") (pintype "passive"))
      (node (ref "JP2") (pin "8") (pinfunction "8_8") (pintype "passive"))
      (node (ref "JP3") (pin "1") (pinfunction "1_1") (pintype "bidirectional"))
      (node (ref "JP3") (pin "5") (pinfunction "5_5") (pintype "bidirectional"))
      (node (ref "JP4") (pin "5") (pinfunction "5_5") (pintype "passive"))
      (node (ref "JP4") (pin "6") (pinfunction "6_6") (pintype "passive"))
      (node (ref "JP4") (pin "8") (pinfunction "8_8") (pintype "passive"))
      (node (ref "JP5") (pin "1") (pinfunction "1_1") (pintype "passive"))
      (node (ref "JP6") (pin "5") (pinfunction "5_5") (pintype "passive"))
      (node (ref "JP6") (pin "6") (pinfunction "6_6") (pintype "passive"))
      (node (ref "JP6") (pin "8") (pinfunction "8_8") (pintype "passive"))
      (node (ref "JP7") (pin "1") (pinfunction "1_1") (pintype "passive"))
      (node (ref "JP8") (pin "5") (pinfunction "5_5") (pintype "passive"))
      (node (ref "JP8") (pin "6") (pinfunction "6_6") (pintype "passive"))
      (node (ref "JP8") (pin "8") (pinfunction "8_8") (pintype "passive"))
      (node (ref "LED1") (pin "C") (pinfunction "C_C") (pintype "passive"))
      (node (ref "LED2") (pin "C") (pinfunction "C_C") (pintype "passive"))
      (node (ref "SW1") (pin "B") (pinfunction "S_B") (pintype "passive"))
      (node (ref "SW1") (pin "B'") (pinfunction "S1_B'") (pintype "passive"))
      (node (ref "U$1") (pin "2") (pinfunction "1_2") (pintype "bidirectional"))
      (node (ref "U$12") (pin "14") (pinfunction "14_14") (pintype "passive"))
      (node (ref "U$2") (pin "1") (pinfunction "GND_1") (pintype "bidirectional"))
      (node (ref "U$3") (pin "2") (pinfunction "1_2") (pintype "bidirectional"))
      (node (ref "U$4") (pin "2") (pinfunction "1_2") (pintype "bidirectional"))
      (node (ref "U$5") (pin "1") (pinfunction "1_1") (pintype "bidirectional"))
      (node (ref "U$7") (pin "GND") (pinfunction "P$4_GND") (pintype "bidirectional"))
      (node (ref "U1") (pin "6") (pinfunction "GND_6") (pintype "bidirectional"))
      (node (ref "U1") (pin "GND1") (pinfunction "SHIELD_GND1") (pintype "bidirectional"))
      (node (ref "U1") (pin "GND2") (pinfunction "SHIELD_GND2") (pintype "bidirectional"))
      (node (ref "X2") (pin "4") (pinfunction "4_4") (pintype "passive"))
      (node (ref "XPOL") (pin "GND") (pinfunction "GND_GND") (pintype "power_in"))
      (node (ref "XPOL") (pin "GND@0") (pinfunction "GND_GND@0") (pintype "power_in"))
      (node (ref "YPOL") (pin "GND") (pinfunction "GND_GND") (pintype "power_in"))
      (node (ref "YPOL") (pin "GND@0") (pinfunction "GND_GND@0") (pintype "power_in"))
      (node (ref "ZPOL") (pin "GND") (pinfunction "GND_GND") (pintype "power_in"))
      (node (ref "ZPOL") (pin "GND@0") (pinfunction "GND_GND@0") (pintype "power_in"))
    )
    (net (code "70") (name "Net-(D4-C)") (class "Default")
      (node (ref "D4") (pin "1") (pinfunction "C_1") (pintype "passive"))
      (node (ref "IC3") (pin "2") (pinfunction "OUT_2") (pintype "output"))
      (node (ref "L3") (pin "1") (pinfunction "1_1") (pintype "passive"))
    )
    (net (code "71") (name "Net-(D7-C)") (class "Default")
      (node (ref "D7") (pin "1") (pinfunction "C_1") (pintype "passive"))
      (node (ref "IC5") (pin "2") (pinfunction "OUT_2") (pintype "output"))
      (node (ref "L2") (pin "1") (pinfunction "1_1") (pintype "passive"))
    )
    (net (code "72") (name "Net-(E1POL-PadMS1)") (class "Default")
      (node (ref "E1POL") (pin "MS1") (pinfunction "MS1_MS1") (pintype "input"))
      (node (ref "E1POL") (pin "MS2") (pinfunction "MS2_MS2") (pintype "input"))
      (node (ref "E1POL") (pin "MS3") (pinfunction "MS3_MS3") (pintype "input"))
      (node (ref "R8") (pin "2") (pinfunction "2_2") (pintype "passive"))
    )
    (net (code "73") (name "Net-(E1POL-SLEEP)") (class "Default")
      (node (ref "E1POL") (pin "RST") (pinfunction "RST_RST") (pintype "input"))
      (node (ref "E1POL") (pin "SLP") (pinfunction "SLEEP_SLP") (pintype "input"))
    )
    (net (code "74") (name "Net-(IC2-AREF)") (class "Default")
      (node (ref "C23") (pin "1") (pinfunction "1_1") (pintype "passive"))
      (node (ref "IC2") (pin "32") (pinfunction "AREF_32") (pintype "passive"))
    )
    (net (code "75") (name "Net-(IC2-XTAL1)") (class "Default")
      (node (ref "C6") (pin "1") (pinfunction "1_1") (pintype "passive"))
      (node (ref "IC2") (pin "13") (pinfunction "XTAL1_13") (pintype "input"))
      (node (ref "Q7") (pin "1") (pinfunction "1_1") (pintype "passive"))
    )
    (net (code "76") (name "Net-(IC2-XTAL2)") (class "Default")
      (node (ref "C5") (pin "1") (pinfunction "1_1") (pintype "passive"))
      (node (ref "IC2") (pin "12") (pinfunction "XTAL2_12") (pintype "output"))
      (node (ref "Q7") (pin "2") (pinfunction "2_2") (pintype "passive"))
    )
    (net (code "77") (name "Net-(LED1-PadA)") (class "Default")
      (node (ref "LED1") (pin "A") (pinfunction "A_A") (pintype "passive"))
      (node (ref "R16") (pin "1") (pinfunction "1_1") (pintype "passive"))
    )
    (net (code "78") (name "Net-(LED2-PadA)") (class "Default")
      (node (ref "LED2") (pin "A") (pinfunction "A_A") (pintype "passive"))
      (node (ref "R9") (pin "2") (pinfunction "2_2") (pintype "passive"))
    )
    (net (code "79") (name "Net-(R5-Pad2)") (class "Default")
      (node (ref "R5") (pin "2") (pinfunction "2_2") (pintype "passive"))
      (node (ref "YPOL") (pin "MS1") (pinfunction "MS1_MS1") (pintype "input"))
      (node (ref "YPOL") (pin "MS2") (pinfunction "MS2_MS2") (pintype "input"))
      (node (ref "YPOL") (pin "MS3") (pinfunction "MS3_MS3") (pintype "input"))
    )
    (net (code "80") (name "Net-(R6-Pad2)") (class "Default")
      (node (ref "R6") (pin "2") (pinfunction "2_2") (pintype "passive"))
      (node (ref "ZPOL") (pin "MS1") (pinfunction "MS1_MS1") (pintype "input"))
      (node (ref "ZPOL") (pin "MS2") (pinfunction "MS2_MS2") (pintype "input"))
      (node (ref "ZPOL") (pin "MS3") (pinfunction "MS3_MS3") (pintype "input"))
    )
    (net (code "81") (name "Net-(R7-Pad2)") (class "Default")
      (node (ref "R7") (pin "2") (pinfunction "2_2") (pintype "passive"))
      (node (ref "XPOL") (pin "MS1") (pinfunction "MS1_MS1") (pintype "input"))
      (node (ref "XPOL") (pin "MS2") (pinfunction "MS2_MS2") (pintype "input"))
      (node (ref "XPOL") (pin "MS3") (pinfunction "MS3_MS3") (pintype "input"))
    )
    (net (code "82") (name "Net-(U$1-2)") (class "Default")
      (node (ref "R20") (pin "2") (pinfunction "2_2") (pintype "passive"))
      (node (ref "U$1") (pin "1") (pinfunction "2_1") (pintype "bidirectional"))
    )
    (net (code "83") (name "Net-(U$2-V3)") (class "Default")
      (node (ref "C21") (pin "1") (pinfunction "1_1") (pintype "passive"))
      (node (ref "U$2") (pin "4") (pinfunction "V3_4") (pintype "bidirectional"))
    )
    (net (code "84") (name "Net-(U$2-XI)") (class "Default")
      (node (ref "12MHZ1") (pin "1") (pinfunction "1_1") (pintype "passive"))
      (node (ref "C16") (pin "1") (pinfunction "1_1") (pintype "passive"))
      (node (ref "U$2") (pin "7") (pinfunction "XI_7") (pintype "bidirectional"))
    )
    (net (code "85") (name "Net-(U$2-XO)") (class "Default")
      (node (ref "12MHZ1") (pin "2") (pinfunction "2_2") (pintype "passive"))
      (node (ref "C17") (pin "1") (pinfunction "1_1") (pintype "passive"))
      (node (ref "U$2") (pin "8") (pinfunction "XO_8") (pintype "bidirectional"))
    )
    (net (code "86") (name "Net-(U$3-2)") (class "Default")
      (node (ref "R1") (pin "2") (pinfunction "2_2") (pintype "passive"))
      (node (ref "U$3") (pin "1") (pinfunction "2_1") (pintype "bidirectional"))
    )
    (net (code "87") (name "Net-(U$4-2)") (class "Default")
      (node (ref "R2") (pin "2") (pinfunction "2_2") (pintype "passive"))
      (node (ref "U$4") (pin "1") (pinfunction "2_1") (pintype "bidirectional"))
    )
    (net (code "88") (name "Net-(XPOL-SLEEP)") (class "Default")
      (node (ref "XPOL") (pin "RST") (pinfunction "RST_RST") (pintype "input"))
      (node (ref "XPOL") (pin "SLP") (pinfunction "SLEEP_SLP") (pintype "input"))
    )
    (net (code "89") (name "Net-(YPOL-SLEEP)") (class "Default")
      (node (ref "YPOL") (pin "RST") (pinfunction "RST_RST") (pintype "input"))
      (node (ref "YPOL") (pin "SLP") (pinfunction "SLEEP_SLP") (pintype "input"))
    )
    (net (code "90") (name "Net-(ZPOL-SLEEP)") (class "Default")
      (node (ref "ZPOL") (pin "RST") (pinfunction "RST_RST") (pintype "input"))
      (node (ref "ZPOL") (pin "SLP") (pinfunction "SLEEP_SLP") (pintype "input"))
    )
    (net (code "91") (name "VCC") (class "Default")
      (node (ref "C10") (pin "1") (pinfunction "1_1") (pintype "passive"))
      (node (ref "C13") (pin "1") (pinfunction "1_1") (pintype "passive"))
      (node (ref "C14") (pin "1") (pinfunction "1_1") (pintype "passive"))
      (node (ref "C18") (pin "1") (pinfunction "1_1") (pintype "passive"))
      (node (ref "C26") (pin "+") (pinfunction "+_+") (pintype "passive"))
      (node (ref "C27") (pin "2") (pinfunction "2_2") (pintype "passive"))
      (node (ref "C30") (pin "+") (pinfunction "+_+") (pintype "passive"))
      (node (ref "C8") (pin "1") (pinfunction "1_1") (pintype "passive"))
      (node (ref "E1POL") (pin "VDD") (pinfunction "VDD_VDD") (pintype "power_in"))
      (node (ref "IC1") (pin "1") (pinfunction "VDD_1") (pintype "power_in"))
      (node (ref "IC2") (pin "10") (pinfunction "VCC_10") (pintype "power_in"))
      (node (ref "IC4") (pin "3") (pinfunction "IN_3") (pintype "input"))
      (node (ref "IC5") (pin "4") (pinfunction "FB_4") (pintype "input"))
      (node (ref "JP1") (pin "3") (pinfunction "3_3") (pintype "passive"))
      (node (ref "JP2") (pin "7") (pinfunction "7_7") (pintype "passive"))
      (node (ref "JP3") (pin "6") (pinfunction "6_6") (pintype "bidirectional"))
      (node (ref "JP4") (pin "7") (pinfunction "7_7") (pintype "passive"))
      (node (ref "JP6") (pin "7") (pinfunction "7_7") (pintype "passive"))
      (node (ref "JP8") (pin "7") (pinfunction "7_7") (pintype "passive"))
      (node (ref "L1") (pin "2") (pinfunction "2_2") (pintype "passive"))
      (node (ref "L2") (pin "2") (pinfunction "2_2") (pintype "passive"))
      (node (ref "R10") (pin "1") (pinfunction "1_1") (pintype "passive"))
      (node (ref "R11") (pin "1") (pinfunction "1_1") (pintype "passive"))
      (node (ref "R16") (pin "2") (pinfunction "2_2") (pintype "passive"))
      (node (ref "R4") (pin "2") (pinfunction "2_2") (pintype "passive"))
      (node (ref "R5") (pin "1") (pinfunction "1_1") (pintype "passive"))
      (node (ref "R6") (pin "1") (pinfunction "1_1") (pintype "passive"))
      (node (ref "R7") (pin "1") (pinfunction "1_1") (pintype "passive"))
      (node (ref "R8") (pin "1") (pinfunction "1_1") (pintype "passive"))
      (node (ref "U$12") (pin "13") (pinfunction "13_13") (pintype "passive"))
      (node (ref "U$7") (pin "VCC") (pinfunction "P$6_VCC") (pintype "bidirectional"))
      (node (ref "XPOL") (pin "VDD") (pinfunction "VDD_VDD") (pintype "power_in"))
      (node (ref "YPOL") (pin "VDD") (pinfunction "VDD_VDD") (pintype "power_in"))
      (node (ref "ZPOL") (pin "VDD") (pinfunction "VDD_VDD") (pintype "power_in"))
    )
    (net (code "92") (name "unconnected-(IC2-PCINT7{slash}ADC7_PA7-Pad33)") (class "Default")
      (node (ref "IC2") (pin "33") (pinfunction "PCINT7/ADC7_PA7_33") (pintype "bidirectional"))
    )
    (net (code "93") (name "unconnected-(IC2-PCINT20{slash}TDO_PC4-Pad26)") (class "Default")
      (node (ref "IC2") (pin "26") (pinfunction "PCINT20/TDO_PC4_26") (pintype "bidirectional"))
    )
    (net (code "94") (name "unconnected-(IC2-PCINT29{slash}OC1A_PD5-Pad19)") (class "Default")
      (node (ref "IC2") (pin "19") (pinfunction "PCINT29/OC1A_PD5_19") (pintype "bidirectional"))
    )
    (net (code "95") (name "unconnected-(U$2-CTS-Pad9)") (class "Default")
      (node (ref "U$2") (pin "9") (pinfunction "CTS_9") (pintype "bidirectional"))
    )
    (net (code "96") (name "unconnected-(U$2-DCD-Pad12)") (class "Default")
      (node (ref "U$2") (pin "12") (pinfunction "DCD_12") (pintype "bidirectional"))
    )
    (net (code "97") (name "unconnected-(U$2-DSR-Pad10)") (class "Default")
      (node (ref "U$2") (pin "10") (pinfunction "DSR_10") (pintype "bidirectional"))
    )
    (net (code "98") (name "unconnected-(U$2-RI-Pad11)") (class "Default")
      (node (ref "U$2") (pin "11") (pinfunction "RI_11") (pintype "bidirectional"))
    )
    (net (code "99") (name "unconnected-(U$2-RS232-Pad15)") (class "Default")
      (node (ref "U$2") (pin "15") (pinfunction "RS232_15") (pintype "bidirectional"))
    )
    (net (code "100") (name "unconnected-(U$2-RTS-Pad14)") (class "Default")
      (node (ref "U$2") (pin "14") (pinfunction "RTS_14") (pintype "bidirectional"))
    )
    (net (code "101") (name "unconnected-(U1-NC-Pad1)") (class "Default")
      (node (ref "U1") (pin "1") (pinfunction "NC_1") (pintype "bidirectional"))
    )
    (net (code "102") (name "unconnected-(U1-RSV-Pad8)") (class "Default")
      (node (ref "U1") (pin "8") (pinfunction "RSV_8") (pintype "bidirectional"))
    )
    (net (code "103") (name "unconnected-(U1-SHIELD-PadCDNC1)") (class "Default")
      (node (ref "U1") (pin "CDNC1") (pinfunction "SHIELD_CDNC1") (pintype "bidirectional"))
    )
    (net (code "104") (name "unconnected-(U1-SHIELD-PadCDNC2)") (class "Default")
      (node (ref "U1") (pin "CDNC2") (pinfunction "SHIELD_CDNC2") (pintype "bidirectional"))
    )
  )
)
